# BarGraphDriver.net
KiCad netlist of a schematic drawn in EAGLE
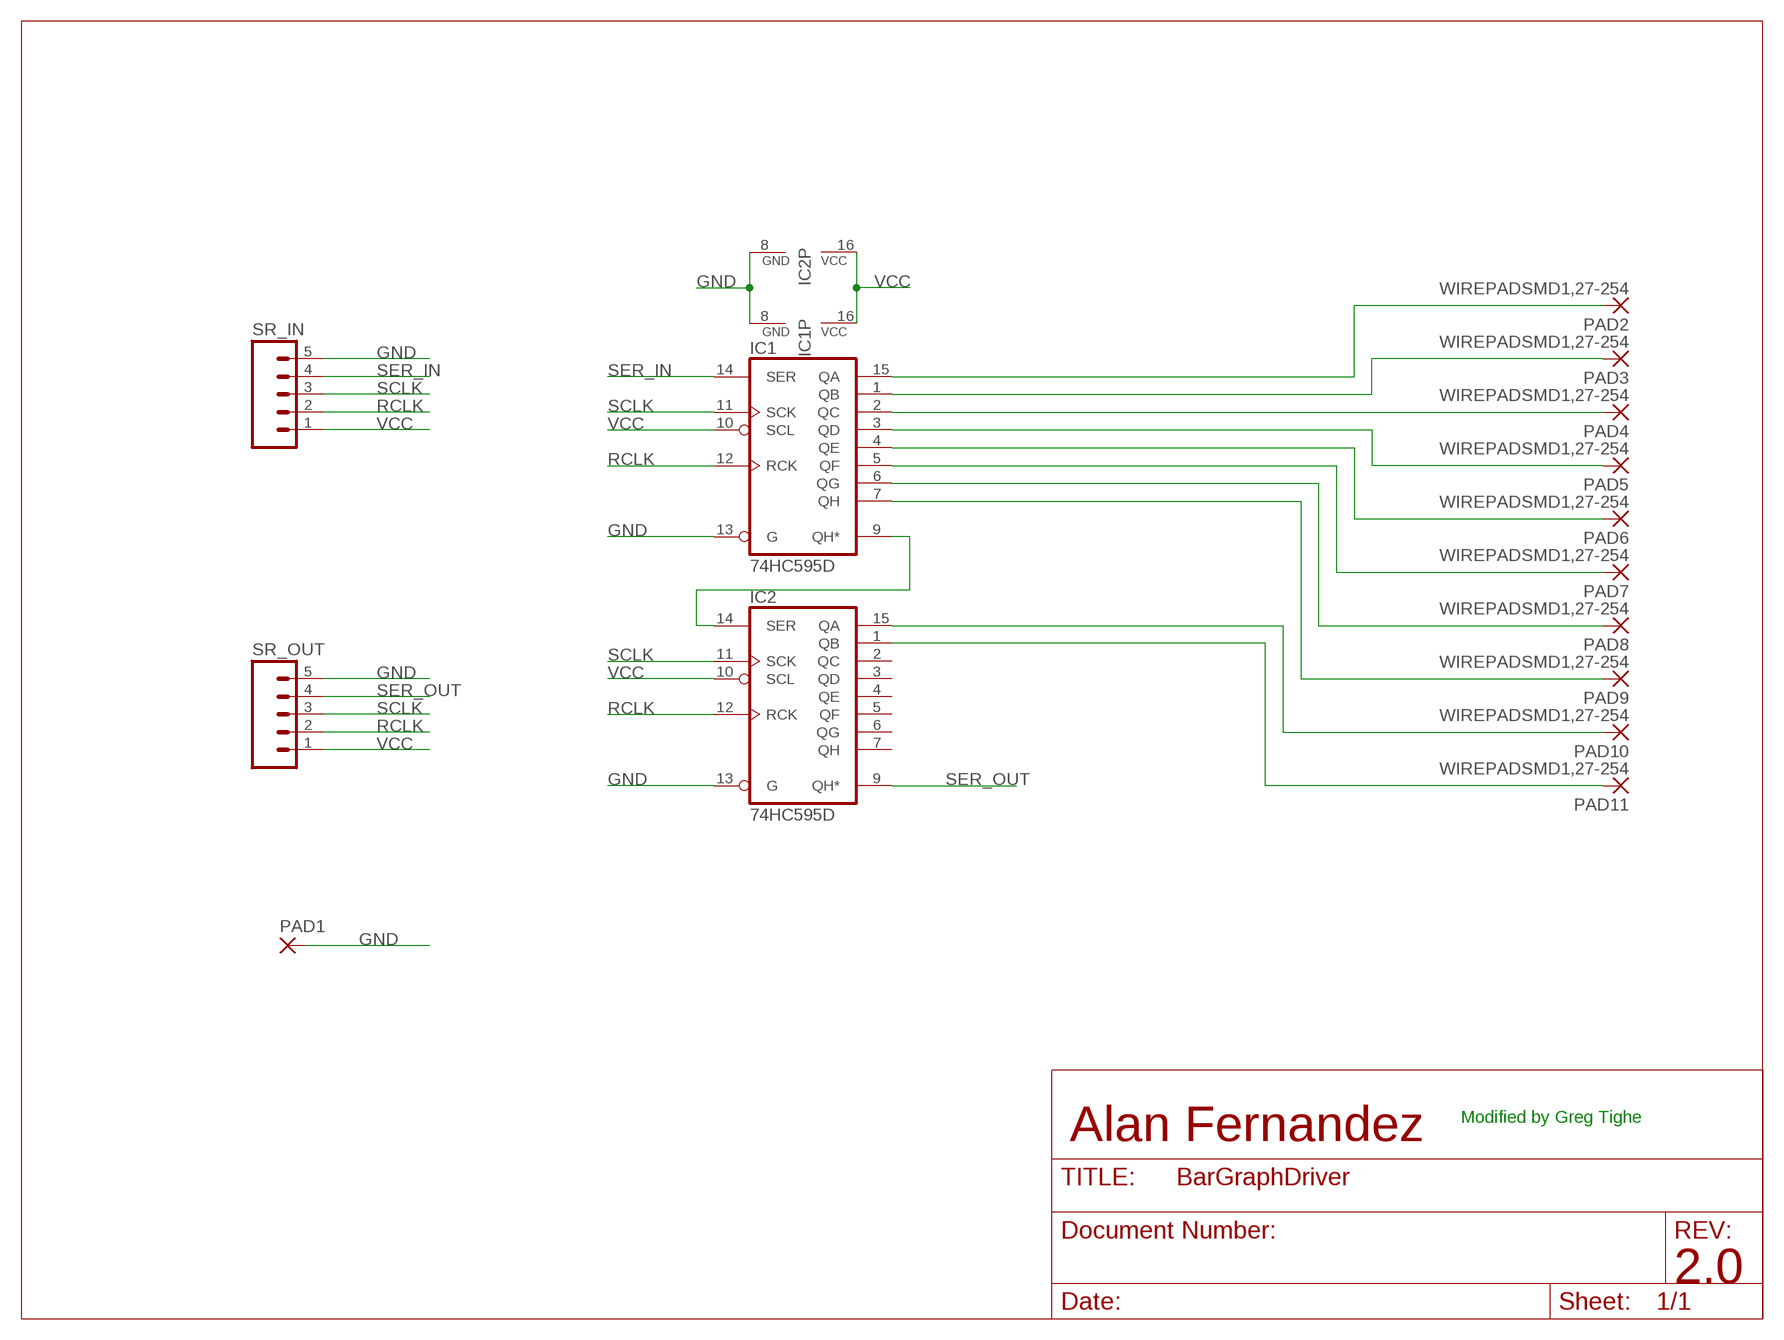
[diagram p0: schematic, sheet 1]

(export (version "E")
  (design (tool "Eeschema 10.0.6"))
  (components
    (comp (ref "IC1")
      (value "74HC595D")
      (footprint "eagle-import:SO16")
      (libsource (lib "eagle-import") (part "74595DHC"))
    )
    (comp (ref "IC2")
      (value "74HC595D")
      (footprint "eagle-import:SO16")
      (libsource (lib "eagle-import") (part "74595DHC"))
    )
    (comp (ref "PAD1")
      (value "SMD2")
      (footprint "eagle-import:SMD1,27-2,54")
      (libsource (lib "eagle-import") (part "SMD2"))
    )
    (comp (ref "PAD2")
      (value "WIREPADSMD1,27-254")
      (footprint "eagle-import:SMD1,27-2,54")
      (libsource (lib "eagle-import") (part "WIREPADSMD1,27-254"))
    )
    (comp (ref "PAD3")
      (value "WIREPADSMD1,27-254")
      (footprint "eagle-import:SMD1,27-2,54")
      (libsource (lib "eagle-import") (part "WIREPADSMD1,27-254"))
    )
    (comp (ref "PAD4")
      (value "WIREPADSMD1,27-254")
      (footprint "eagle-import:SMD1,27-2,54")
      (libsource (lib "eagle-import") (part "WIREPADSMD1,27-254"))
    )
    (comp (ref "PAD5")
      (value "WIREPADSMD1,27-254")
      (footprint "eagle-import:SMD1,27-2,54")
      (libsource (lib "eagle-import") (part "WIREPADSMD1,27-254"))
    )
    (comp (ref "PAD6")
      (value "WIREPADSMD1,27-254")
      (footprint "eagle-import:SMD1,27-2,54")
      (libsource (lib "eagle-import") (part "WIREPADSMD1,27-254"))
    )
    (comp (ref "PAD7")
      (value "WIREPADSMD1,27-254")
      (footprint "eagle-import:SMD1,27-2,54")
      (libsource (lib "eagle-import") (part "WIREPADSMD1,27-254"))
    )
    (comp (ref "PAD8")
      (value "WIREPADSMD1,27-254")
      (footprint "eagle-import:SMD1,27-2,54")
      (libsource (lib "eagle-import") (part "WIREPADSMD1,27-254"))
    )
    (comp (ref "PAD9")
      (value "WIREPADSMD1,27-254")
      (footprint "eagle-import:SMD1,27-2,54")
      (libsource (lib "eagle-import") (part "WIREPADSMD1,27-254"))
    )
    (comp (ref "PAD10")
      (value "WIREPADSMD1,27-254")
      (footprint "eagle-import:SMD1,27-2,54")
      (libsource (lib "eagle-import") (part "WIREPADSMD1,27-254"))
    )
    (comp (ref "PAD11")
      (value "WIREPADSMD1,27-254")
      (footprint "eagle-import:SMD1,27-2,54")
      (libsource (lib "eagle-import") (part "WIREPADSMD1,27-254"))
    )
    (comp (ref "SR_IN")
      (value "M05PTH")
      (footprint "eagle-import:1X05")
      (libsource (lib "eagle-import") (part "M05PTH"))
    )
    (comp (ref "SR_OUT")
      (value "M05PTH")
      (footprint "eagle-import:1X05")
      (libsource (lib "eagle-import") (part "M05PTH"))
    )
  )
  (nets
    (net (code "1") (name "/GND") (class "Default")
      (node (ref "IC1") (pin "13") (pinfunction "G_13") (pintype "input"))
      (node (ref "IC1") (pin "8") (pinfunction "GND_8") (pintype "power_in"))
      (node (ref "IC2") (pin "13") (pinfunction "G_13") (pintype "input"))
      (node (ref "IC2") (pin "8") (pinfunction "GND_8") (pintype "power_in"))
      (node (ref "PAD1") (pin "1") (pinfunction "P_1") (pintype "passive"))
      (node (ref "SR_IN") (pin "5") (pinfunction "5_5") (pintype "passive"))
      (node (ref "SR_OUT") (pin "5") (pinfunction "5_5") (pintype "passive"))
    )
    (net (code "2") (name "/RCLK") (class "Default")
      (node (ref "IC1") (pin "12") (pinfunction "RCK_12") (pintype "input"))
      (node (ref "IC2") (pin "12") (pinfunction "RCK_12") (pintype "input"))
      (node (ref "SR_IN") (pin "2") (pinfunction "2_2") (pintype "passive"))
      (node (ref "SR_OUT") (pin "2") (pinfunction "2_2") (pintype "passive"))
    )
    (net (code "3") (name "/SCLK") (class "Default")
      (node (ref "IC1") (pin "11") (pinfunction "SCK_11") (pintype "input"))
      (node (ref "IC2") (pin "11") (pinfunction "SCK_11") (pintype "input"))
      (node (ref "SR_IN") (pin "3") (pinfunction "3_3") (pintype "passive"))
      (node (ref "SR_OUT") (pin "3") (pinfunction "3_3") (pintype "passive"))
    )
    (net (code "4") (name "/SER_IN") (class "Default")
      (node (ref "IC1") (pin "14") (pinfunction "SER_14") (pintype "input"))
      (node (ref "SR_IN") (pin "4") (pinfunction "4_4") (pintype "passive"))
    )
    (net (code "5") (name "/SER_OUT") (class "Default")
      (node (ref "IC2") (pin "9") (pinfunction "QH*_9") (pintype "tri_state"))
      (node (ref "SR_OUT") (pin "4") (pinfunction "4_4") (pintype "passive"))
    )
    (net (code "6") (name "/VCC") (class "Default")
      (node (ref "IC1") (pin "10") (pinfunction "SCL_10") (pintype "input"))
      (node (ref "IC1") (pin "16") (pinfunction "VCC_16") (pintype "power_in"))
      (node (ref "IC2") (pin "10") (pinfunction "SCL_10") (pintype "input"))
      (node (ref "IC2") (pin "16") (pinfunction "VCC_16") (pintype "power_in"))
      (node (ref "SR_IN") (pin "1") (pinfunction "1_1") (pintype "passive"))
      (node (ref "SR_OUT") (pin "1") (pinfunction "1_1") (pintype "passive"))
    )
    (net (code "7") (name "Net-(IC1A-QA)") (class "Default")
      (node (ref "IC1") (pin "15") (pinfunction "QA_15") (pintype "tri_state"))
      (node (ref "PAD2") (pin "1") (pinfunction "P_1") (pintype "passive"))
    )
    (net (code "8") (name "Net-(IC1A-QB)") (class "Default")
      (node (ref "IC1") (pin "1") (pinfunction "QB_1") (pintype "tri_state"))
      (node (ref "PAD3") (pin "1") (pinfunction "P_1") (pintype "passive"))
    )
    (net (code "9") (name "Net-(IC1A-QC)") (class "Default")
      (node (ref "IC1") (pin "2") (pinfunction "QC_2") (pintype "tri_state"))
      (node (ref "PAD4") (pin "1") (pinfunction "P_1") (pintype "passive"))
    )
    (net (code "10") (name "Net-(IC1A-QD)") (class "Default")
      (node (ref "IC1") (pin "3") (pinfunction "QD_3") (pintype "tri_state"))
      (node (ref "PAD5") (pin "1") (pinfunction "P_1") (pintype "passive"))
    )
    (net (code "11") (name "Net-(IC1A-QE)") (class "Default")
      (node (ref "IC1") (pin "4") (pinfunction "QE_4") (pintype "tri_state"))
      (node (ref "PAD6") (pin "1") (pinfunction "P_1") (pintype "passive"))
    )
    (net (code "12") (name "Net-(IC1A-QF)") (class "Default")
      (node (ref "IC1") (pin "5") (pinfunction "QF_5") (pintype "tri_state"))
      (node (ref "PAD7") (pin "1") (pinfunction "P_1") (pintype "passive"))
    )
    (net (code "13") (name "Net-(IC1A-QG)") (class "Default")
      (node (ref "IC1") (pin "6") (pinfunction "QG_6") (pintype "tri_state"))
      (node (ref "PAD8") (pin "1") (pinfunction "P_1") (pintype "passive"))
    )
    (net (code "14") (name "Net-(IC1A-QH)") (class "Default")
      (node (ref "IC1") (pin "7") (pinfunction "QH_7") (pintype "tri_state"))
      (node (ref "PAD9") (pin "1") (pinfunction "P_1") (pintype "passive"))
    )
    (net (code "15") (name "Net-(IC1A-QH*)") (class "Default")
      (node (ref "IC1") (pin "9") (pinfunction "QH*_9") (pintype "tri_state"))
      (node (ref "IC2") (pin "14") (pinfunction "SER_14") (pintype "input"))
    )
    (net (code "16") (name "Net-(IC2A-QA)") (class "Default")
      (node (ref "IC2") (pin "15") (pinfunction "QA_15") (pintype "tri_state"))
      (node (ref "PAD10") (pin "1") (pinfunction "P_1") (pintype "passive"))
    )
    (net (code "17") (name "Net-(IC2A-QB)") (class "Default")
      (node (ref "IC2") (pin "1") (pinfunction "QB_1") (pintype "tri_state"))
      (node (ref "PAD11") (pin "1") (pinfunction "P_1") (pintype "passive"))
    )
    (net (code "18") (name "unconnected-(IC2A-QC-Pad2)") (class "Default")
      (node (ref "IC2") (pin "2") (pinfunction "QC_2") (pintype "tri_state"))
    )
    (net (code "19") (name "unconnected-(IC2A-QD-Pad3)") (class "Default")
      (node (ref "IC2") (pin "3") (pinfunction "QD_3") (pintype "tri_state"))
    )
    (net (code "20") (name "unconnected-(IC2A-QE-Pad4)") (class "Default")
      (node (ref "IC2") (pin "4") (pinfunction "QE_4") (pintype "tri_state"))
    )
    (net (code "21") (name "unconnected-(IC2A-QF-Pad5)") (class "Default")
      (node (ref "IC2") (pin "5") (pinfunction "QF_5") (pintype "tri_state"))
    )
    (net (code "22") (name "unconnected-(IC2A-QG-Pad6)") (class "Default")
      (node (ref "IC2") (pin "6") (pinfunction "QG_6") (pintype "tri_state"))
    )
    (net (code "23") (name "unconnected-(IC2A-QH-Pad7)") (class "Default")
      (node (ref "IC2") (pin "7") (pinfunction "QH_7") (pintype "tri_state"))
    )
  )
)
